# GL852-3.net
KiCad netlist of a schematic drawn in Altium Designer
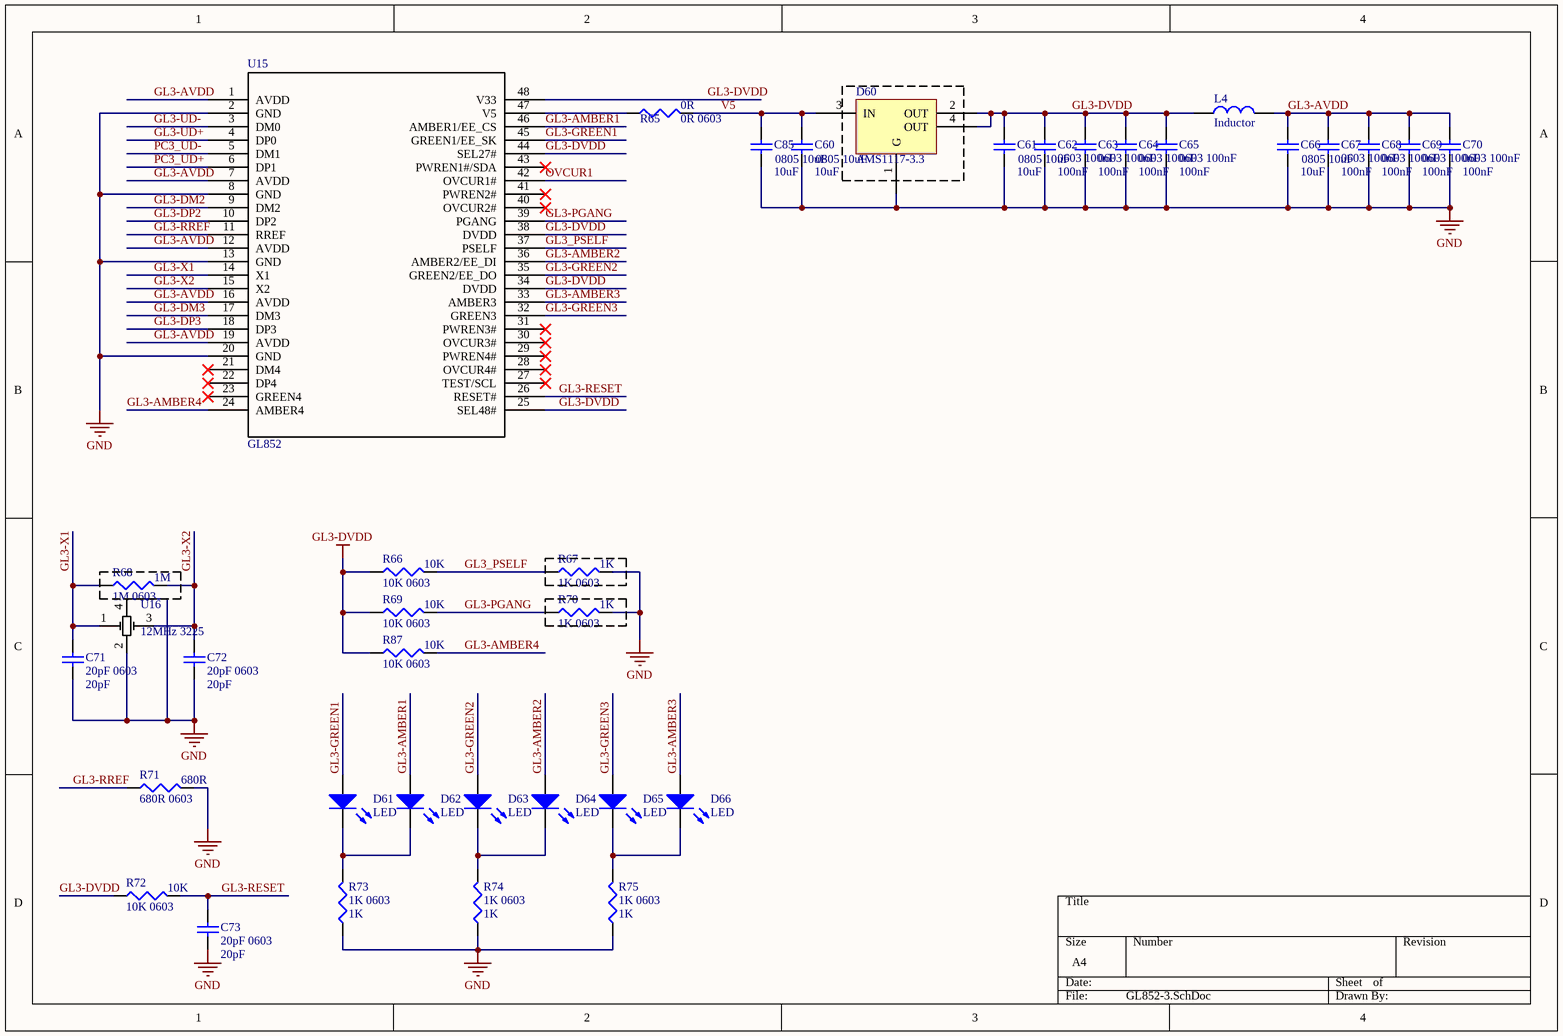
[diagram p0: GL852-3.SchDoc]

(export (version "E")
  (design (tool "Eeschema 10.0.6"))
  (components
    (comp (ref "C60")
      (value "0805 10uF")
      (footprint "C0805")
      (description "Capacitor (Semiconductor SIM Model)")
      (fields (field (name "ALTIUM_VALUE") "10uF") (field (name "PUBLISHER") "Altium Limited"))
      (libsource (lib "Miscellaneous Devices") (part "Cap Semi"))
    )
    (comp (ref "C61")
      (value "0805 10uF")
      (footprint "C0805")
      (description "Capacitor (Semiconductor SIM Model)")
      (fields (field (name "ALTIUM_VALUE") "10uF") (field (name "PUBLISHER") "Altium Limited"))
      (libsource (lib "Miscellaneous Devices") (part "Cap Semi"))
    )
    (comp (ref "C62")
      (value "0603 100nF")
      (footprint "C0603")
      (description "Capacitor (Semiconductor SIM Model)")
      (fields (field (name "ALTIUM_VALUE") "100nF") (field (name "PUBLISHER") "Altium Limited"))
      (libsource (lib "Miscellaneous Devices") (part "Cap Semi"))
    )
    (comp (ref "C63")
      (value "0603 100nF")
      (footprint "C0603")
      (description "Capacitor (Semiconductor SIM Model)")
      (fields (field (name "ALTIUM_VALUE") "100nF") (field (name "PUBLISHER") "Altium Limited"))
      (libsource (lib "Miscellaneous Devices") (part "Cap Semi"))
    )
    (comp (ref "C64")
      (value "0603 100nF")
      (footprint "C0603")
      (description "Capacitor (Semiconductor SIM Model)")
      (fields (field (name "ALTIUM_VALUE") "100nF") (field (name "PUBLISHER") "Altium Limited"))
      (libsource (lib "Miscellaneous Devices") (part "Cap Semi"))
    )
    (comp (ref "C65")
      (value "0603 100nF")
      (footprint "C0603")
      (description "Capacitor (Semiconductor SIM Model)")
      (fields (field (name "ALTIUM_VALUE") "100nF") (field (name "PUBLISHER") "Altium Limited"))
      (libsource (lib "Miscellaneous Devices") (part "Cap Semi"))
    )
    (comp (ref "C66")
      (value "0805 10uF")
      (footprint "C0805")
      (description "Capacitor (Semiconductor SIM Model)")
      (fields (field (name "ALTIUM_VALUE") "10uF") (field (name "PUBLISHER") "Altium Limited"))
      (libsource (lib "Miscellaneous Devices") (part "Cap Semi"))
    )
    (comp (ref "C67")
      (value "0603 100nF")
      (footprint "C0603")
      (description "Capacitor (Semiconductor SIM Model)")
      (fields (field (name "ALTIUM_VALUE") "100nF") (field (name "PUBLISHER") "Altium Limited"))
      (libsource (lib "Miscellaneous Devices") (part "Cap Semi"))
    )
    (comp (ref "C68")
      (value "0603 100nF")
      (footprint "C0603")
      (description "Capacitor (Semiconductor SIM Model)")
      (fields (field (name "ALTIUM_VALUE") "100nF") (field (name "PUBLISHER") "Altium Limited"))
      (libsource (lib "Miscellaneous Devices") (part "Cap Semi"))
    )
    (comp (ref "C69")
      (value "0603 100nF")
      (footprint "C0603")
      (description "Capacitor (Semiconductor SIM Model)")
      (fields (field (name "ALTIUM_VALUE") "100nF") (field (name "PUBLISHER") "Altium Limited"))
      (libsource (lib "Miscellaneous Devices") (part "Cap Semi"))
    )
    (comp (ref "C70")
      (value "0603 100nF")
      (footprint "C0603")
      (description "Capacitor (Semiconductor SIM Model)")
      (fields (field (name "ALTIUM_VALUE") "100nF") (field (name "PUBLISHER") "Altium Limited"))
      (libsource (lib "Miscellaneous Devices") (part "Cap Semi"))
    )
    (comp (ref "C71")
      (value "20pF 0603")
      (footprint "C0603")
      (description "Capacitor (Semiconductor SIM Model)")
      (fields (field (name "ALTIUM_VALUE") "20pF") (field (name "PUBLISHER") "Altium Limited"))
      (libsource (lib "Miscellaneous Devices") (part "Cap Semi"))
    )
    (comp (ref "C72")
      (value "20pF 0603")
      (footprint "C0603")
      (description "Capacitor (Semiconductor SIM Model)")
      (fields (field (name "ALTIUM_VALUE") "20pF") (field (name "PUBLISHER") "Altium Limited"))
      (libsource (lib "Miscellaneous Devices") (part "Cap Semi"))
    )
    (comp (ref "C73")
      (value "20pF 0603")
      (footprint "C0603")
      (description "Capacitor (Semiconductor SIM Model)")
      (fields (field (name "ALTIUM_VALUE") "20pF") (field (name "PUBLISHER") "Altium Limited"))
      (libsource (lib "Miscellaneous Devices") (part "Cap Semi"))
    )
    (comp (ref "C85")
      (value "0805 10uF")
      (footprint "C0805")
      (description "Capacitor (Semiconductor SIM Model)")
      (fields (field (name "ALTIUM_VALUE") "10uF") (field (name "PUBLISHER") "Altium Limited"))
      (libsource (lib "Miscellaneous Devices") (part "Cap Semi"))
    )
    (comp (ref "D60")
      (value "AMS1117-3.3")
      (footprint "SOT-223")
      (libsource (lib "MyLib") (part "AMS1117-3.3"))
    )
    (comp (ref "D61") (value "LED") (footprint "LED0603") (libsource (lib "Common Device") (part "LED")))
    (comp (ref "D62") (value "LED") (footprint "LED0603") (libsource (lib "Common Device") (part "LED")))
    (comp (ref "D63") (value "LED") (footprint "LED0603") (libsource (lib "Common Device") (part "LED")))
    (comp (ref "D64") (value "LED") (footprint "LED0603") (libsource (lib "Common Device") (part "LED")))
    (comp (ref "D65") (value "LED") (footprint "LED0603") (libsource (lib "Common Device") (part "LED")))
    (comp (ref "D66") (value "LED") (footprint "LED0603") (libsource (lib "Common Device") (part "LED")))
    (comp (ref "L4")
      (value "Inductor")
      (footprint "L0603")
      (libsource (lib "Common Device") (part "Inductor"))
    )
    (comp (ref "R65")
      (value "0R 0603")
      (footprint "R0603")
      (description "Resistor")
      (fields (field (name "ALTIUM_VALUE") "0R") (field (name "PUBLISHER") "Altium Limited"))
      (libsource (lib "Miscellaneous Devices") (part "Res3"))
    )
    (comp (ref "R66")
      (value "10K 0603")
      (footprint "R0603")
      (description "Resistor")
      (fields (field (name "ALTIUM_VALUE") "10K") (field (name "PUBLISHER") "Altium Limited"))
      (libsource (lib "Miscellaneous Devices") (part "Res3"))
    )
    (comp (ref "R67")
      (value "1K 0603")
      (footprint "R0603")
      (description "Resistor")
      (fields (field (name "ALTIUM_VALUE") "1K") (field (name "PUBLISHER") "Altium Limited"))
      (libsource (lib "Miscellaneous Devices") (part "Res3"))
    )
    (comp (ref "R68")
      (value "1M 0603")
      (footprint "R0603")
      (description "Resistor")
      (fields (field (name "ALTIUM_VALUE") "1M") (field (name "PUBLISHER") "Altium Limited"))
      (libsource (lib "Miscellaneous Devices") (part "Res3"))
    )
    (comp (ref "R69")
      (value "10K 0603")
      (footprint "R0603")
      (description "Resistor")
      (fields (field (name "ALTIUM_VALUE") "10K") (field (name "PUBLISHER") "Altium Limited"))
      (libsource (lib "Miscellaneous Devices") (part "Res3"))
    )
    (comp (ref "R70")
      (value "1K 0603")
      (footprint "R0603")
      (description "Resistor")
      (fields (field (name "ALTIUM_VALUE") "1K") (field (name "PUBLISHER") "Altium Limited"))
      (libsource (lib "Miscellaneous Devices") (part "Res3"))
    )
    (comp (ref "R71")
      (value "680R 0603")
      (footprint "R0603")
      (description "Resistor")
      (fields (field (name "ALTIUM_VALUE") "680R") (field (name "PUBLISHER") "Altium Limited"))
      (libsource (lib "Miscellaneous Devices") (part "Res3"))
    )
    (comp (ref "R72")
      (value "10K 0603")
      (footprint "R0603")
      (description "Resistor")
      (fields (field (name "ALTIUM_VALUE") "10K") (field (name "PUBLISHER") "Altium Limited"))
      (libsource (lib "Miscellaneous Devices") (part "Res3"))
    )
    (comp (ref "R73")
      (value "1K 0603")
      (footprint "R0603")
      (description "Resistor")
      (fields (field (name "ALTIUM_VALUE") "1K") (field (name "PUBLISHER") "Altium Limited"))
      (libsource (lib "Miscellaneous Devices") (part "Res3"))
    )
    (comp (ref "R74")
      (value "1K 0603")
      (footprint "R0603")
      (description "Resistor")
      (fields (field (name "ALTIUM_VALUE") "1K") (field (name "PUBLISHER") "Altium Limited"))
      (libsource (lib "Miscellaneous Devices") (part "Res3"))
    )
    (comp (ref "R75")
      (value "1K 0603")
      (footprint "R0603")
      (description "Resistor")
      (fields (field (name "ALTIUM_VALUE") "1K") (field (name "PUBLISHER") "Altium Limited"))
      (libsource (lib "Miscellaneous Devices") (part "Res3"))
    )
    (comp (ref "R87")
      (value "10K 0603")
      (footprint "R0603")
      (description "Resistor")
      (fields (field (name "ALTIUM_VALUE") "10K") (field (name "PUBLISHER") "Altium Limited"))
      (libsource (lib "Miscellaneous Devices") (part "Res3"))
    )
    (comp (ref "U15")
      (value "GL852")
      (footprint "qfp48-20-0909b")
      (description "Imported")
      (libsource (lib "USB-new-component") (part "GL852"))
    )
    (comp (ref "U16")
      (value "12MHz 3225")
      (footprint "XTAL-3225")
      (libsource (lib "XTAL3225") (part "Component_1"))
    )
  )
  (nets
    (net (code "1") (name "/GL3-AMBER1") (class "Default")
      (node (ref "D62") (pin "1") (pinfunction "A_1") (pintype "passive"))
      (node (ref "U15") (pin "46") (pinfunction "AMBER1/EE_CS_46") (pintype "passive"))
    )
    (net (code "2") (name "/GL3-AMBER2") (class "Default")
      (node (ref "D64") (pin "1") (pinfunction "A_1") (pintype "passive"))
      (node (ref "U15") (pin "36") (pinfunction "AMBER2/EE_DI_36") (pintype "passive"))
    )
    (net (code "3") (name "/GL3-AMBER3") (class "Default")
      (node (ref "D66") (pin "1") (pinfunction "A_1") (pintype "passive"))
      (node (ref "U15") (pin "33") (pinfunction "AMBER3_33") (pintype "passive"))
    )
    (net (code "4") (name "/GL3-AMBER4") (class "Default")
      (node (ref "R87") (pin "2") (pinfunction "2_2") (pintype "passive"))
      (node (ref "U15") (pin "24") (pinfunction "AMBER4_24") (pintype "passive"))
    )
    (net (code "5") (name "/GL3-AVDD") (class "Default")
      (node (ref "C66") (pin "2") (pinfunction "2_2") (pintype "passive"))
      (node (ref "C67") (pin "2") (pinfunction "2_2") (pintype "passive"))
      (node (ref "C68") (pin "2") (pinfunction "2_2") (pintype "passive"))
      (node (ref "C69") (pin "2") (pinfunction "2_2") (pintype "passive"))
      (node (ref "C70") (pin "2") (pinfunction "2_2") (pintype "passive"))
      (node (ref "L4") (pin "2") (pinfunction "2_2") (pintype "passive"))
      (node (ref "U15") (pin "1") (pinfunction "AVDD_1") (pintype "passive"))
      (node (ref "U15") (pin "12") (pinfunction "AVDD_12") (pintype "passive"))
      (node (ref "U15") (pin "16") (pinfunction "AVDD_16") (pintype "passive"))
      (node (ref "U15") (pin "19") (pinfunction "AVDD_19") (pintype "passive"))
      (node (ref "U15") (pin "7") (pinfunction "AVDD_7") (pintype "passive"))
    )
    (net (code "6") (name "/GL3-DM2") (class "Default")
      (node (ref "U15") (pin "9") (pinfunction "DM2_9") (pintype "passive"))
    )
    (net (code "7") (name "/GL3-DM3") (class "Default")
      (node (ref "U15") (pin "17") (pinfunction "DM3_17") (pintype "passive"))
    )
    (net (code "8") (name "/GL3-DP2") (class "Default")
      (node (ref "U15") (pin "10") (pinfunction "DP2_10") (pintype "passive"))
    )
    (net (code "9") (name "/GL3-DP3") (class "Default")
      (node (ref "U15") (pin "18") (pinfunction "DP3_18") (pintype "passive"))
    )
    (net (code "10") (name "/GL3-GREEN1") (class "Default")
      (node (ref "D61") (pin "1") (pinfunction "A_1") (pintype "passive"))
      (node (ref "U15") (pin "45") (pinfunction "GREEN1/EE_SK_45") (pintype "passive"))
    )
    (net (code "11") (name "/GL3-GREEN2") (class "Default")
      (node (ref "D63") (pin "1") (pinfunction "A_1") (pintype "passive"))
      (node (ref "U15") (pin "35") (pinfunction "GREEN2/EE_DO_35") (pintype "passive"))
    )
    (net (code "12") (name "/GL3-GREEN3") (class "Default")
      (node (ref "D65") (pin "1") (pinfunction "A_1") (pintype "passive"))
      (node (ref "U15") (pin "32") (pinfunction "GREEN3_32") (pintype "passive"))
    )
    (net (code "13") (name "/GL3-PGANG") (class "Default")
      (node (ref "R69") (pin "2") (pinfunction "2_2") (pintype "passive"))
      (node (ref "R70") (pin "1") (pinfunction "1_1") (pintype "passive"))
      (node (ref "U15") (pin "39") (pinfunction "PGANG_39") (pintype "passive"))
    )
    (net (code "14") (name "/GL3-RESET") (class "Default")
      (node (ref "C73") (pin "2") (pinfunction "2_2") (pintype "passive"))
      (node (ref "R72") (pin "2") (pinfunction "2_2") (pintype "passive"))
      (node (ref "U15") (pin "26") (pinfunction "RESET#_26") (pintype "passive"))
    )
    (net (code "15") (name "/GL3-RREF") (class "Default")
      (node (ref "R71") (pin "1") (pinfunction "1_1") (pintype "passive"))
      (node (ref "U15") (pin "11") (pinfunction "RREF_11") (pintype "passive"))
    )
    (net (code "16") (name "/GL3-UD+") (class "Default")
      (node (ref "U15") (pin "4") (pinfunction "DP0_4") (pintype "passive"))
    )
    (net (code "17") (name "/GL3-UD-") (class "Default")
      (node (ref "U15") (pin "3") (pinfunction "DM0_3") (pintype "passive"))
    )
    (net (code "18") (name "/GL3-X1") (class "Default")
      (node (ref "C71") (pin "2") (pinfunction "2_2") (pintype "passive"))
      (node (ref "R68") (pin "1") (pinfunction "1_1") (pintype "passive"))
      (node (ref "U15") (pin "14") (pinfunction "X1_14") (pintype "passive"))
      (node (ref "U16") (pin "1") (pinfunction "1_1") (pintype "passive"))
    )
    (net (code "19") (name "/GL3-X2") (class "Default")
      (node (ref "C72") (pin "2") (pinfunction "2_2") (pintype "passive"))
      (node (ref "R68") (pin "2") (pinfunction "2_2") (pintype "passive"))
      (node (ref "U15") (pin "15") (pinfunction "X2_15") (pintype "passive"))
      (node (ref "U16") (pin "3") (pinfunction "3_3") (pintype "passive"))
    )
    (net (code "20") (name "/GL3_PSELF") (class "Default")
      (node (ref "R66") (pin "2") (pinfunction "2_2") (pintype "passive"))
      (node (ref "R67") (pin "1") (pinfunction "1_1") (pintype "passive"))
      (node (ref "U15") (pin "37") (pinfunction "PSELF_37") (pintype "passive"))
    )
    (net (code "21") (name "/OVCUR1") (class "Default")
      (node (ref "U15") (pin "42") (pinfunction "OVCUR1#_42") (pintype "passive"))
    )
    (net (code "22") (name "/PC3_UD+") (class "Default")
      (node (ref "U15") (pin "6") (pinfunction "DP1_6") (pintype "passive"))
    )
    (net (code "23") (name "/PC3_UD-") (class "Default")
      (node (ref "U15") (pin "5") (pinfunction "DM1_5") (pintype "passive"))
    )
    (net (code "24") (name "/V5") (class "Default")
      (node (ref "C60") (pin "2") (pinfunction "2_2") (pintype "passive"))
      (node (ref "C85") (pin "2") (pinfunction "2_2") (pintype "passive"))
      (node (ref "D60") (pin "3") (pinfunction "IN_3") (pintype "passive"))
      (node (ref "R65") (pin "2") (pinfunction "2_2") (pintype "passive"))
    )
    (net (code "25") (name "GL3-DVDD") (class "Default")
      (node (ref "C61") (pin "2") (pinfunction "2_2") (pintype "passive"))
      (node (ref "C62") (pin "2") (pinfunction "2_2") (pintype "passive"))
      (node (ref "C63") (pin "2") (pinfunction "2_2") (pintype "passive"))
      (node (ref "C64") (pin "2") (pinfunction "2_2") (pintype "passive"))
      (node (ref "C65") (pin "2") (pinfunction "2_2") (pintype "passive"))
      (node (ref "D60") (pin "2") (pinfunction "OUT_2") (pintype "passive"))
      (node (ref "D60") (pin "4") (pinfunction "OUT_4") (pintype "passive"))
      (node (ref "L4") (pin "1") (pinfunction "1_1") (pintype "passive"))
      (node (ref "R66") (pin "1") (pinfunction "1_1") (pintype "passive"))
      (node (ref "R69") (pin "1") (pinfunction "1_1") (pintype "passive"))
      (node (ref "R72") (pin "1") (pinfunction "1_1") (pintype "passive"))
      (node (ref "R87") (pin "1") (pinfunction "1_1") (pintype "passive"))
      (node (ref "U15") (pin "25") (pinfunction "SEL48#_25") (pintype "passive"))
      (node (ref "U15") (pin "34") (pinfunction "DVDD_34") (pintype "passive"))
      (node (ref "U15") (pin "38") (pinfunction "DVDD_38") (pintype "passive"))
      (node (ref "U15") (pin "44") (pinfunction "SEL27#_44") (pintype "passive"))
      (node (ref "U15") (pin "48") (pinfunction "V33_48") (pintype "passive"))
    )
    (net (code "26") (name "GND") (class "Default")
      (node (ref "C60") (pin "1") (pinfunction "1_1") (pintype "passive"))
      (node (ref "C61") (pin "1") (pinfunction "1_1") (pintype "passive"))
      (node (ref "C62") (pin "1") (pinfunction "1_1") (pintype "passive"))
      (node (ref "C63") (pin "1") (pinfunction "1_1") (pintype "passive"))
      (node (ref "C64") (pin "1") (pinfunction "1_1") (pintype "passive"))
      (node (ref "C65") (pin "1") (pinfunction "1_1") (pintype "passive"))
      (node (ref "C66") (pin "1") (pinfunction "1_1") (pintype "passive"))
      (node (ref "C67") (pin "1") (pinfunction "1_1") (pintype "passive"))
      (node (ref "C68") (pin "1") (pinfunction "1_1") (pintype "passive"))
      (node (ref "C69") (pin "1") (pinfunction "1_1") (pintype "passive"))
      (node (ref "C70") (pin "1") (pinfunction "1_1") (pintype "passive"))
      (node (ref "C71") (pin "1") (pinfunction "1_1") (pintype "passive"))
      (node (ref "C72") (pin "1") (pinfunction "1_1") (pintype "passive"))
      (node (ref "C73") (pin "1") (pinfunction "1_1") (pintype "passive"))
      (node (ref "C85") (pin "1") (pinfunction "1_1") (pintype "passive"))
      (node (ref "D60") (pin "1") (pinfunction "G_1") (pintype "passive"))
      (node (ref "R67") (pin "2") (pinfunction "2_2") (pintype "passive"))
      (node (ref "R70") (pin "2") (pinfunction "2_2") (pintype "passive"))
      (node (ref "R71") (pin "2") (pinfunction "2_2") (pintype "passive"))
      (node (ref "R73") (pin "1") (pinfunction "1_1") (pintype "passive"))
      (node (ref "R74") (pin "1") (pinfunction "1_1") (pintype "passive"))
      (node (ref "R75") (pin "1") (pinfunction "1_1") (pintype "passive"))
      (node (ref "U15") (pin "13") (pinfunction "GND_13") (pintype "passive"))
      (node (ref "U15") (pin "2") (pinfunction "GND_2") (pintype "passive"))
      (node (ref "U15") (pin "20") (pinfunction "GND_20") (pintype "passive"))
      (node (ref "U15") (pin "8") (pinfunction "GND_8") (pintype "passive"))
      (node (ref "U16") (pin "2") (pinfunction "2_2") (pintype "passive"))
      (node (ref "U16") (pin "4") (pinfunction "4_4") (pintype "passive"))
    )
    (net (code "27") (name "Net-(D61-K)") (class "Default")
      (node (ref "D61") (pin "2") (pinfunction "K_2") (pintype "passive"))
      (node (ref "D62") (pin "2") (pinfunction "K_2") (pintype "passive"))
      (node (ref "R73") (pin "2") (pinfunction "2_2") (pintype "passive"))
    )
    (net (code "28") (name "Net-(D63-K)") (class "Default")
      (node (ref "D63") (pin "2") (pinfunction "K_2") (pintype "passive"))
      (node (ref "D64") (pin "2") (pinfunction "K_2") (pintype "passive"))
      (node (ref "R74") (pin "2") (pinfunction "2_2") (pintype "passive"))
    )
    (net (code "29") (name "Net-(D65-K)") (class "Default")
      (node (ref "D65") (pin "2") (pinfunction "K_2") (pintype "passive"))
      (node (ref "D66") (pin "2") (pinfunction "K_2") (pintype "passive"))
      (node (ref "R75") (pin "2") (pinfunction "2_2") (pintype "passive"))
    )
    (net (code "30") (name "Net-(U15-V5)") (class "Default")
      (node (ref "R65") (pin "1") (pinfunction "1_1") (pintype "passive"))
      (node (ref "U15") (pin "47") (pinfunction "V5_47") (pintype "passive"))
    )
    (net (code "31") (name "unconnected-(U15-DM4-Pad21)") (class "Default")
      (node (ref "U15") (pin "21") (pinfunction "DM4_21") (pintype "passive+no_connect"))
    )
    (net (code "32") (name "unconnected-(U15-DP4-Pad22)") (class "Default")
      (node (ref "U15") (pin "22") (pinfunction "DP4_22") (pintype "passive+no_connect"))
    )
    (net (code "33") (name "unconnected-(U15-GREEN4-Pad23)") (class "Default")
      (node (ref "U15") (pin "23") (pinfunction "GREEN4_23") (pintype "passive+no_connect"))
    )
    (net (code "34") (name "unconnected-(U15-OVCUR2#-Pad40)") (class "Default")
      (node (ref "U15") (pin "40") (pinfunction "OVCUR2#_40") (pintype "passive+no_connect"))
    )
    (net (code "35") (name "unconnected-(U15-OVCUR3#-Pad30)") (class "Default")
      (node (ref "U15") (pin "30") (pinfunction "OVCUR3#_30") (pintype "passive+no_connect"))
    )
    (net (code "36") (name "unconnected-(U15-OVCUR4#-Pad28)") (class "Default")
      (node (ref "U15") (pin "28") (pinfunction "OVCUR4#_28") (pintype "passive+no_connect"))
    )
    (net (code "37") (name "unconnected-(U15-PWREN1#{slash}SDA-Pad43)") (class "Default")
      (node (ref "U15") (pin "43") (pinfunction "PWREN1#/SDA_43") (pintype "passive+no_connect"))
    )
    (net (code "38") (name "unconnected-(U15-PWREN2#-Pad41)") (class "Default")
      (node (ref "U15") (pin "41") (pinfunction "PWREN2#_41") (pintype "passive+no_connect"))
    )
    (net (code "39") (name "unconnected-(U15-PWREN3#-Pad31)") (class "Default")
      (node (ref "U15") (pin "31") (pinfunction "PWREN3#_31") (pintype "passive+no_connect"))
    )
    (net (code "40") (name "unconnected-(U15-PWREN4#-Pad29)") (class "Default")
      (node (ref "U15") (pin "29") (pinfunction "PWREN4#_29") (pintype "passive+no_connect"))
    )
    (net (code "41") (name "unconnected-(U15-TEST{slash}SCL-Pad27)") (class "Default")
      (node (ref "U15") (pin "27") (pinfunction "TEST/SCL_27") (pintype "passive+no_connect"))
    )
  )
)
